# MomoinololuM3.net
KiCad netlist of a schematic drawn in EAGLE
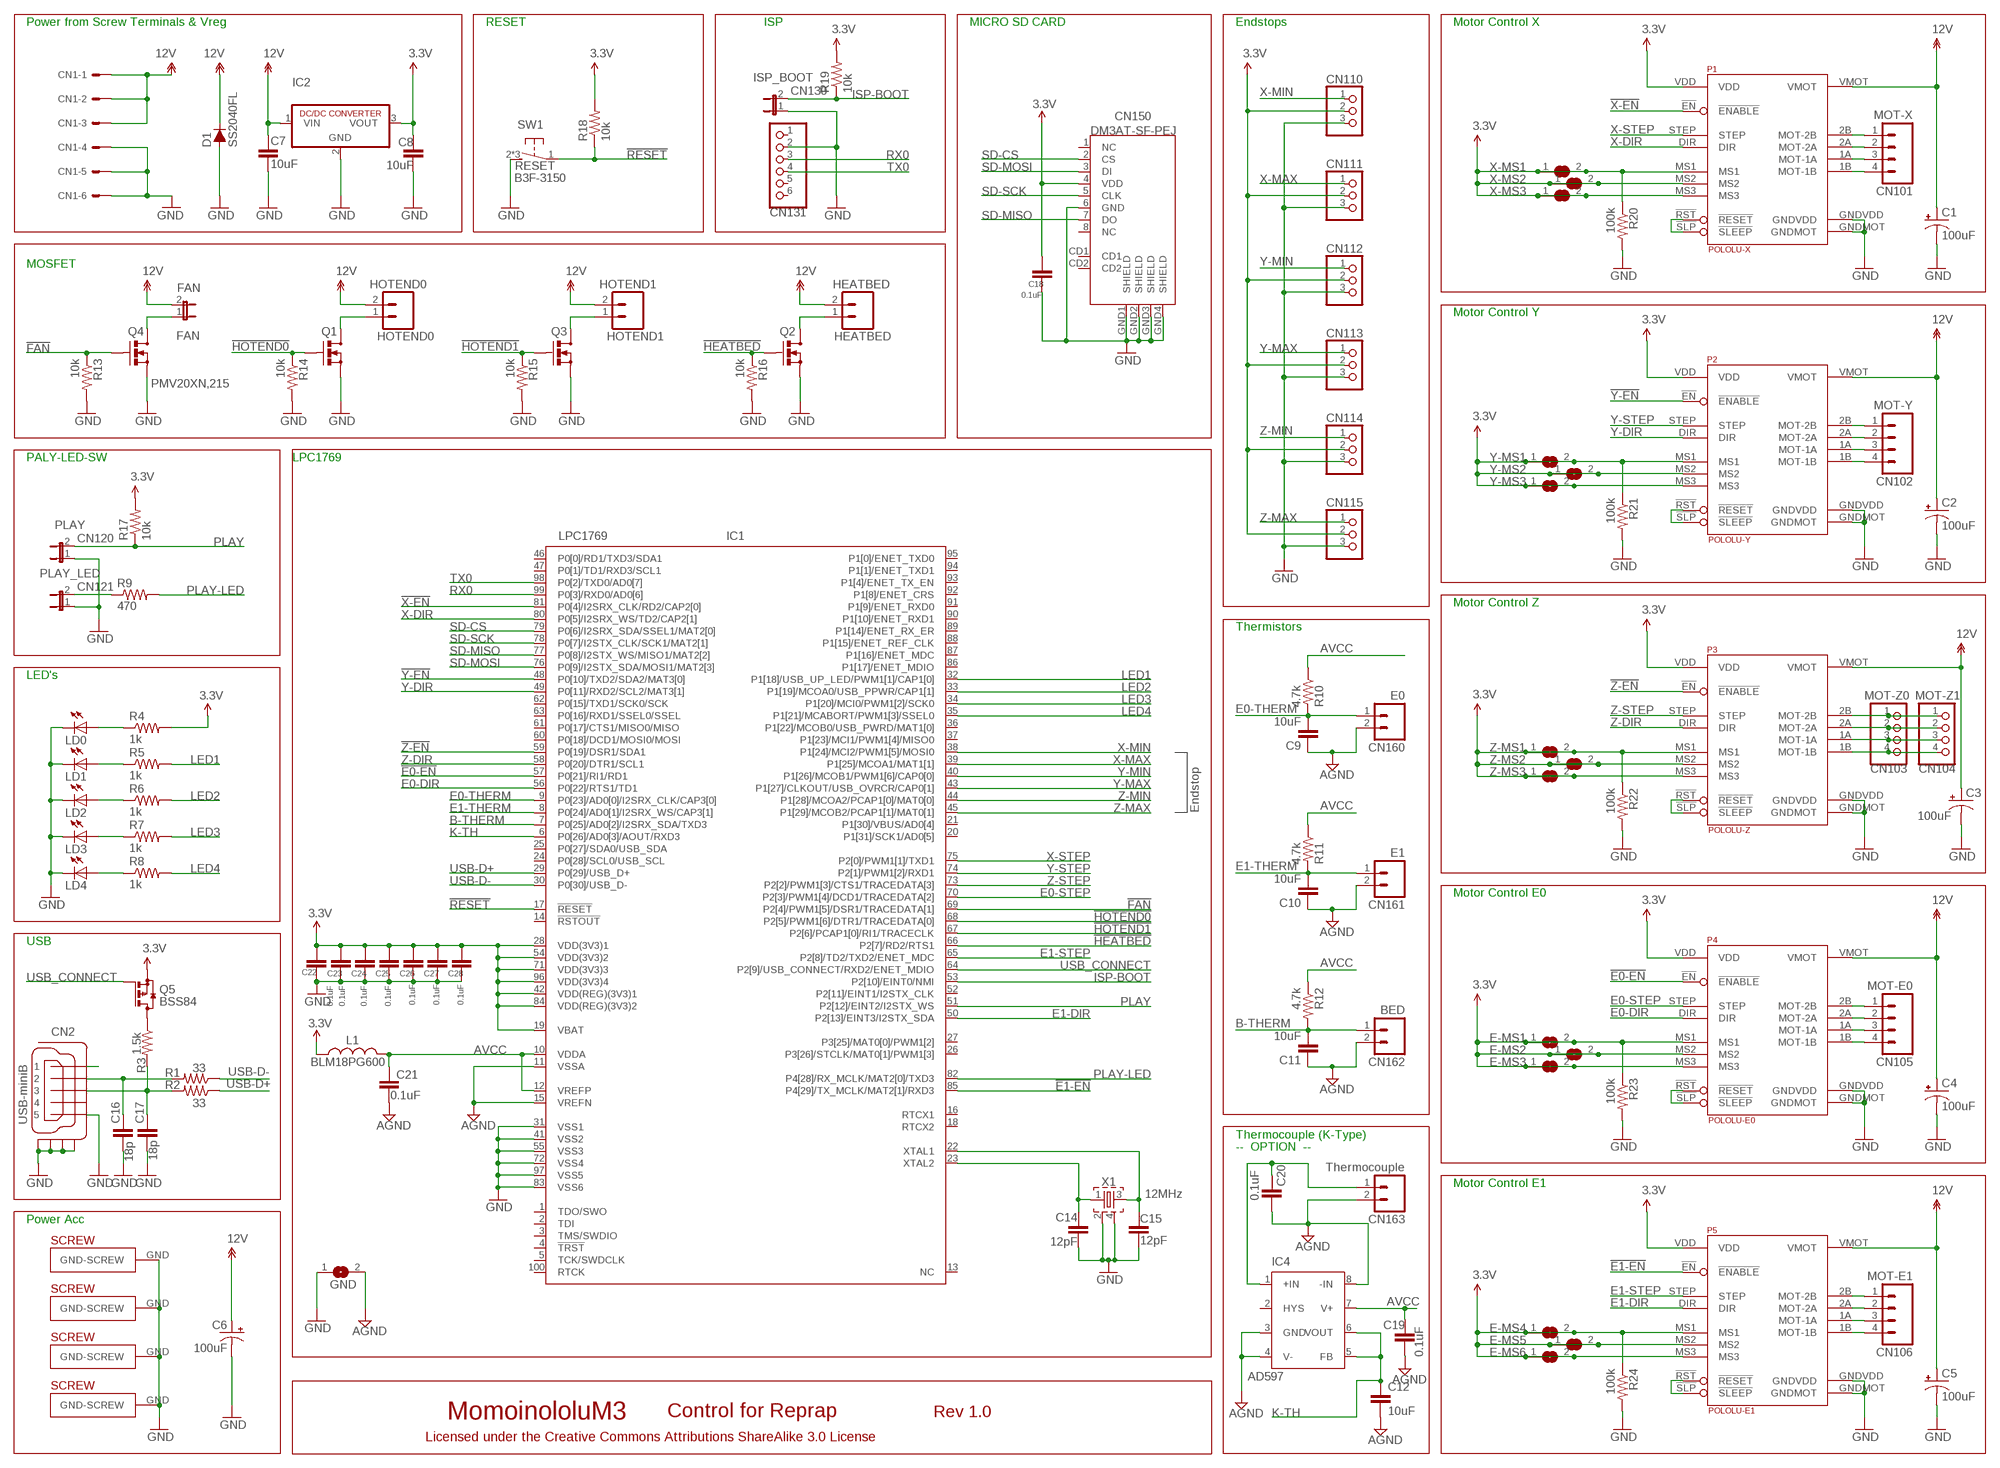
[diagram p0: schematic, sheet 1]

(export (version "E")
  (design (tool "Eeschema 10.0.6"))
  (components
    (comp (ref "C1")
      (value "100uF")
      (footprint "eagle-import:UD-6,3X7,7_NICHICON")
      (libsource (lib "eagle-import") (part "CPOL-USUD-6,3X7,7"))
    )
    (comp (ref "C2")
      (value "100uF")
      (footprint "eagle-import:UD-6,3X7,7_NICHICON")
      (libsource (lib "eagle-import") (part "CPOL-USUD-6,3X7,7"))
    )
    (comp (ref "C3")
      (value "100uF")
      (footprint "eagle-import:UD-6,3X7,7_NICHICON")
      (libsource (lib "eagle-import") (part "CPOL-USUD-6,3X7,7"))
    )
    (comp (ref "C4")
      (value "100uF")
      (footprint "eagle-import:UD-6,3X7,7_NICHICON")
      (libsource (lib "eagle-import") (part "CPOL-USUD-6,3X7,7"))
    )
    (comp (ref "C5")
      (value "100uF")
      (footprint "eagle-import:UD-6,3X7,7_NICHICON")
      (libsource (lib "eagle-import") (part "CPOL-USUD-6,3X7,7"))
    )
    (comp (ref "C6")
      (value "100uF")
      (footprint "eagle-import:UD-6,3X7,7_NICHICON")
      (libsource (lib "eagle-import") (part "CPOL-USUD-6,3X7,7"))
    )
    (comp (ref "C7")
      (value "10uF")
      (footprint "eagle-import:RCL_C1206K")
      (libsource (lib "eagle-import") (part "RCL_C-EUC1206K"))
    )
    (comp (ref "C8")
      (value "10uF")
      (footprint "eagle-import:RCL_C1206K")
      (libsource (lib "eagle-import") (part "RCL_C-EUC1206K"))
    )
    (comp (ref "C9")
      (value "10uF")
      (footprint "eagle-import:RCL_C1206K")
      (libsource (lib "eagle-import") (part "RCL_C-EUC1206K"))
    )
    (comp (ref "C10")
      (value "10uF")
      (footprint "eagle-import:RCL_C1206K")
      (libsource (lib "eagle-import") (part "RCL_C-EUC1206K"))
    )
    (comp (ref "C11")
      (value "10uF")
      (footprint "eagle-import:RCL_C1206K")
      (libsource (lib "eagle-import") (part "RCL_C-EUC1206K"))
    )
    (comp (ref "C12")
      (value "10uF")
      (footprint "eagle-import:RCL_C1206K")
      (libsource (lib "eagle-import") (part "RCL_C-EUC1206K"))
    )
    (comp (ref "C14")
      (value "12pF")
      (footprint "eagle-import:C0603")
      (libsource (lib "eagle-import") (part "C-EUC0603"))
    )
    (comp (ref "C15")
      (value "12pF")
      (footprint "eagle-import:C0603")
      (libsource (lib "eagle-import") (part "C-EUC0603"))
    )
    (comp (ref "C16")
      (value "18p")
      (footprint "eagle-import:C0603")
      (libsource (lib "eagle-import") (part "C-EUC0603"))
    )
    (comp (ref "C17")
      (value "18p")
      (footprint "eagle-import:C0603")
      (libsource (lib "eagle-import") (part "C-EUC0603"))
    )
    (comp (ref "C18")
      (value "0.1uF")
      (footprint "eagle-import:C0603")
      (libsource (lib "eagle-import") (part "C-EUC0603"))
    )
    (comp (ref "C19")
      (value "0.1uF")
      (footprint "eagle-import:C0603")
      (libsource (lib "eagle-import") (part "C-EUC0603"))
    )
    (comp (ref "C20")
      (value "0.1uF")
      (footprint "eagle-import:C0603")
      (libsource (lib "eagle-import") (part "C-EUC0603"))
    )
    (comp (ref "C21")
      (value "0.1uF")
      (footprint "eagle-import:C0603")
      (libsource (lib "eagle-import") (part "C-EUC0603"))
    )
    (comp (ref "C22")
      (value "0.1uF")
      (footprint "eagle-import:C0603")
      (libsource (lib "eagle-import") (part "C-EUC0603"))
    )
    (comp (ref "C23")
      (value "0.1uF")
      (footprint "eagle-import:C0603")
      (libsource (lib "eagle-import") (part "C-EUC0603"))
    )
    (comp (ref "C24")
      (value "0.1uF")
      (footprint "eagle-import:C0603")
      (libsource (lib "eagle-import") (part "C-EUC0603"))
    )
    (comp (ref "C25")
      (value "0.1uF")
      (footprint "eagle-import:C0603")
      (libsource (lib "eagle-import") (part "C-EUC0603"))
    )
    (comp (ref "C26")
      (value "0.1uF")
      (footprint "eagle-import:C0603")
      (libsource (lib "eagle-import") (part "C-EUC0603"))
    )
    (comp (ref "C27")
      (value "0.1uF")
      (footprint "eagle-import:C0603")
      (libsource (lib "eagle-import") (part "C-EUC0603"))
    )
    (comp (ref "C28")
      (value "0.1uF")
      (footprint "eagle-import:C0603")
      (libsource (lib "eagle-import") (part "C-EUC0603"))
    )
    (comp (ref "CN1")
      (value "556X-6H")
      (footprint "eagle-import:5569-6")
      (libsource (lib "eagle-import") (part "556X-6H"))
    )
    (comp (ref "CN2")
      (value "USB-miniB")
      (footprint "eagle-import:CON-HIROSE_UX60A-MB-5ST")
      (libsource (lib "eagle-import") (part "CON-HIROSE_MINI-USB-SHIELD-UX60A-MB-5ST"))
    )
    (comp (ref "CN101")
      (value "MOT-X")
      (footprint "eagle-import:SPARKFUN_MOLEX-1X4")
      (libsource (lib "eagle-import") (part "SPARKFUN_M04POLAR"))
    )
    (comp (ref "CN102")
      (value "MOT-Y")
      (footprint "eagle-import:SPARKFUN_MOLEX-1X4")
      (libsource (lib "eagle-import") (part "SPARKFUN_M04POLAR"))
    )
    (comp (ref "CN103")
      (value "MOT-Z0")
      (footprint "eagle-import:1X04")
      (libsource (lib "eagle-import") (part "PINHD-1X4"))
    )
    (comp (ref "CN104")
      (value "MOT-Z1")
      (footprint "eagle-import:1X04")
      (libsource (lib "eagle-import") (part "PINHD-1X4"))
    )
    (comp (ref "CN105")
      (value "MOT-E0")
      (footprint "eagle-import:SPARKFUN_MOLEX-1X4")
      (libsource (lib "eagle-import") (part "SPARKFUN_M04POLAR"))
    )
    (comp (ref "CN106")
      (value "MOT-E1")
      (footprint "eagle-import:SPARKFUN_MOLEX-1X4")
      (libsource (lib "eagle-import") (part "SPARKFUN_M04POLAR"))
    )
    (comp (ref "CN110")
      (value "PINHD-1X3")
      (footprint "eagle-import:1X03")
      (libsource (lib "eagle-import") (part "PINHD-1X3"))
    )
    (comp (ref "CN111")
      (value "PINHD-1X3")
      (footprint "eagle-import:1X03")
      (libsource (lib "eagle-import") (part "PINHD-1X3"))
    )
    (comp (ref "CN112")
      (value "PINHD-1X3")
      (footprint "eagle-import:1X03")
      (libsource (lib "eagle-import") (part "PINHD-1X3"))
    )
    (comp (ref "CN113")
      (value "PINHD-1X3")
      (footprint "eagle-import:1X03")
      (libsource (lib "eagle-import") (part "PINHD-1X3"))
    )
    (comp (ref "CN114")
      (value "PINHD-1X3")
      (footprint "eagle-import:1X03")
      (libsource (lib "eagle-import") (part "PINHD-1X3"))
    )
    (comp (ref "CN115")
      (value "PINHD-1X3")
      (footprint "eagle-import:1X03")
      (libsource (lib "eagle-import") (part "PINHD-1X3"))
    )
    (comp (ref "CN120")
      (value "PLAY")
      (footprint "eagle-import:SPARKFUN_1X02")
      (libsource (lib "eagle-import") (part "SPARKFUN_JUMPER-2PTH"))
    )
    (comp (ref "CN121")
      (value "PLAY_LED")
      (footprint "eagle-import:SPARKFUN_1X02")
      (libsource (lib "eagle-import") (part "SPARKFUN_JUMPER-2PTH"))
    )
    (comp (ref "CN130")
      (value "ISP_BOOT")
      (footprint "eagle-import:SPARKFUN_1X02")
      (libsource (lib "eagle-import") (part "SPARKFUN_JUMPER-2PTH"))
    )
    (comp (ref "CN131")
      (value "PINHD-1X6")
      (footprint "eagle-import:1X06")
      (libsource (lib "eagle-import") (part "PINHD-1X6"))
    )
    (comp (ref "CN150")
      (value "DM3AT-SF-PEJ")
      (footprint "eagle-import:DM3AT-SF-PEJ")
      (libsource (lib "eagle-import") (part "DM3AT-SF-PEJ"))
    )
    (comp (ref "CN160")
      (value "E0")
      (footprint "eagle-import:SPARKFUN_1X02")
      (libsource (lib "eagle-import") (part "momoinololuM3_SPARKFUN_M02PTH"))
    )
    (comp (ref "CN161")
      (value "E1")
      (footprint "eagle-import:SPARKFUN_1X02")
      (libsource (lib "eagle-import") (part "momoinololuM3_SPARKFUN_M02PTH"))
    )
    (comp (ref "CN162")
      (value "BED")
      (footprint "eagle-import:SPARKFUN_1X02")
      (libsource (lib "eagle-import") (part "momoinololuM3_SPARKFUN_M02PTH"))
    )
    (comp (ref "CN163")
      (value "Thermocouple")
      (footprint "eagle-import:SPARKFUN_1X02")
      (libsource (lib "eagle-import") (part "momoinololuM3_SPARKFUN_M02PTH"))
    )
    (comp (ref "D1")
      (value "SS2040FL")
      (footprint "eagle-import:SEMICON-SMD-IPC_SOD123")
      (libsource (lib "eagle-import") (part "SEMICON-SMD-IPC_D-FILL-SOD123"))
    )
    (comp (ref "E-MS1")
      (value "SJ")
      (footprint "eagle-import:SJ")
      (libsource (lib "eagle-import") (part "SJ"))
    )
    (comp (ref "E-MS2")
      (value "SJ")
      (footprint "eagle-import:SJ")
      (libsource (lib "eagle-import") (part "SJ"))
    )
    (comp (ref "E-MS3")
      (value "SJ")
      (footprint "eagle-import:SJ")
      (libsource (lib "eagle-import") (part "SJ"))
    )
    (comp (ref "E-MS4")
      (value "SJ")
      (footprint "eagle-import:SJ")
      (libsource (lib "eagle-import") (part "SJ"))
    )
    (comp (ref "E-MS5")
      (value "SJ")
      (footprint "eagle-import:SJ")
      (libsource (lib "eagle-import") (part "SJ"))
    )
    (comp (ref "E-MS6")
      (value "SJ")
      (footprint "eagle-import:SJ")
      (libsource (lib "eagle-import") (part "SJ"))
    )
    (comp (ref "FAN")
      (value "FAN")
      (footprint "eagle-import:SPARKFUN_1X02")
      (libsource (lib "eagle-import") (part "SPARKFUN_JUMPER-2PTH"))
    )
    (comp (ref "GND") (value "SJ") (footprint "eagle-import:SJ") (libsource (lib "eagle-import") (part "SJ")))
    (comp (ref "HEATBED")
      (value "HEATBED")
      (footprint "eagle-import:SCREWTERMINAL-5.08MM-2")
      (libsource (lib "eagle-import") (part "SPARKFUN_M025.08MM"))
    )
    (comp (ref "HOLE1")
      (value "PLATED-SCREW")
      (footprint "eagle-import:PLATEDSCREW")
      (libsource (lib "eagle-import") (part "PLATED-SCREW"))
    )
    (comp (ref "HOLE2")
      (value "PLATED-SCREW")
      (footprint "eagle-import:PLATEDSCREW")
      (libsource (lib "eagle-import") (part "PLATED-SCREW"))
    )
    (comp (ref "HOLE3")
      (value "PLATED-SCREW")
      (footprint "eagle-import:PLATEDSCREW")
      (libsource (lib "eagle-import") (part "PLATED-SCREW"))
    )
    (comp (ref "HOLE4")
      (value "PLATED-SCREW")
      (footprint "eagle-import:PLATEDSCREW")
      (libsource (lib "eagle-import") (part "PLATED-SCREW"))
    )
    (comp (ref "HOTEND0")
      (value "HOTEND0")
      (footprint "eagle-import:SCREWTERMINAL-5.08MM-2")
      (libsource (lib "eagle-import") (part "SPARKFUN_M025.08MM"))
    )
    (comp (ref "HOTEND1")
      (value "HOTEND1")
      (footprint "eagle-import:SCREWTERMINAL-5.08MM-2")
      (libsource (lib "eagle-import") (part "SPARKFUN_M025.08MM"))
    )
    (comp (ref "IC1")
      (value "LPC1769")
      (footprint "eagle-import:LQFP100-14X14")
      (libsource (lib "eagle-import") (part "LPC1768"))
    )
    (comp (ref "IC2")
      (value "R-78E3.3-0.5")
      (footprint "eagle-import:SIP3")
      (libsource (lib "eagle-import") (part "R-78C-1.03.3"))
    )
    (comp (ref "IC4")
      (value "AD597")
      (footprint "eagle-import:SO8")
      (libsource (lib "eagle-import") (part "AD597"))
    )
    (comp (ref "L1")
      (value "BLM18PG600")
      (footprint "eagle-import:L2012C")
      (libsource (lib "eagle-import") (part "L-USL2012C"))
    )
    (comp (ref "LD0")
      (value "LEDSML0805")
      (footprint "eagle-import:SML0805")
      (libsource (lib "eagle-import") (part "LEDSML0805"))
    )
    (comp (ref "LD1")
      (value "LEDSML0805")
      (footprint "eagle-import:SML0805")
      (libsource (lib "eagle-import") (part "LEDSML0805"))
    )
    (comp (ref "LD2")
      (value "LEDSML0805")
      (footprint "eagle-import:SML0805")
      (libsource (lib "eagle-import") (part "LEDSML0805"))
    )
    (comp (ref "LD3")
      (value "LEDSML0805")
      (footprint "eagle-import:SML0805")
      (libsource (lib "eagle-import") (part "LEDSML0805"))
    )
    (comp (ref "LD4")
      (value "LEDSML0805")
      (footprint "eagle-import:SML0805")
      (libsource (lib "eagle-import") (part "LEDSML0805"))
    )
    (comp (ref "P1")
      (value "POLOLU-X")
      (footprint "eagle-import:POLOLU-ALLEGRO_POLOLU-ALLEGRO-PTH")
      (libsource (lib "eagle-import") (part "POLOLU-ALLEGRO_POLOLU-ALLEGRO"))
    )
    (comp (ref "P2")
      (value "POLOLU-Y")
      (footprint "eagle-import:POLOLU-ALLEGRO_POLOLU-ALLEGRO-PTH")
      (libsource (lib "eagle-import") (part "POLOLU-ALLEGRO_POLOLU-ALLEGRO"))
    )
    (comp (ref "P3")
      (value "POLOLU-Z")
      (footprint "eagle-import:POLOLU-ALLEGRO_POLOLU-ALLEGRO-PTH")
      (libsource (lib "eagle-import") (part "POLOLU-ALLEGRO_POLOLU-ALLEGRO"))
    )
    (comp (ref "P4")
      (value "POLOLU-E0")
      (footprint "eagle-import:POLOLU-ALLEGRO_POLOLU-ALLEGRO-PTH")
      (libsource (lib "eagle-import") (part "POLOLU-ALLEGRO_POLOLU-ALLEGRO"))
    )
    (comp (ref "P5")
      (value "POLOLU-E1")
      (footprint "eagle-import:POLOLU-ALLEGRO_POLOLU-ALLEGRO-PTH")
      (libsource (lib "eagle-import") (part "POLOLU-ALLEGRO_POLOLU-ALLEGRO"))
    )
    (comp (ref "Q1")
      (value "PSMN038-100YLX")
      (footprint "eagle-import:SOT669")
      (libsource (lib "eagle-import") (part "SPARKFUN_MOSFET-NCHANNELSOT669"))
    )
    (comp (ref "Q2")
      (value "PSMN038-100YLX")
      (footprint "eagle-import:SOT669")
      (libsource (lib "eagle-import") (part "SPARKFUN_MOSFET-NCHANNELSOT669"))
    )
    (comp (ref "Q3")
      (value "PSMN038-100YLX")
      (footprint "eagle-import:SOT669")
      (libsource (lib "eagle-import") (part "SPARKFUN_MOSFET-NCHANNELSOT669"))
    )
    (comp (ref "Q4")
      (value "PMV20XN,215")
      (footprint "eagle-import:SPARKFUN_SOT23-3")
      (libsource (lib "eagle-import") (part "momoinololuM3_SPARKFUN_MOSFET-NCHANNELSMD"))
    )
    (comp (ref "Q5")
      (value "BSS84")
      (footprint "eagle-import:SOT23")
      (libsource (lib "eagle-import") (part "BSS84"))
    )
    (comp (ref "R1")
      (value "33")
      (footprint "eagle-import:R0603")
      (libsource (lib "eagle-import") (part "R-US_R0603"))
    )
    (comp (ref "R2")
      (value "33")
      (footprint "eagle-import:R0603")
      (libsource (lib "eagle-import") (part "R-US_R0603"))
    )
    (comp (ref "R3")
      (value "1.5k")
      (footprint "eagle-import:R0603")
      (libsource (lib "eagle-import") (part "R-US_R0603"))
    )
    (comp (ref "R4")
      (value "1k")
      (footprint "eagle-import:R0603")
      (libsource (lib "eagle-import") (part "R-US_R0603"))
    )
    (comp (ref "R5")
      (value "1k")
      (footprint "eagle-import:R0603")
      (libsource (lib "eagle-import") (part "R-US_R0603"))
    )
    (comp (ref "R6")
      (value "1k")
      (footprint "eagle-import:R0603")
      (libsource (lib "eagle-import") (part "R-US_R0603"))
    )
    (comp (ref "R7")
      (value "1k")
      (footprint "eagle-import:R0603")
      (libsource (lib "eagle-import") (part "R-US_R0603"))
    )
    (comp (ref "R8")
      (value "1k")
      (footprint "eagle-import:R0603")
      (libsource (lib "eagle-import") (part "R-US_R0603"))
    )
    (comp (ref "R9")
      (value "470")
      (footprint "eagle-import:R0603")
      (libsource (lib "eagle-import") (part "R-US_R0603"))
    )
    (comp (ref "R10")
      (value "4.7k")
      (footprint "eagle-import:R0603")
      (libsource (lib "eagle-import") (part "R-US_R0603"))
    )
    (comp (ref "R11")
      (value "4.7k")
      (footprint "eagle-import:R0603")
      (libsource (lib "eagle-import") (part "R-US_R0603"))
    )
    (comp (ref "R12")
      (value "4.7k")
      (footprint "eagle-import:R0603")
      (libsource (lib "eagle-import") (part "R-US_R0603"))
    )
    (comp (ref "R13")
      (value "10k")
      (footprint "eagle-import:R0603")
      (libsource (lib "eagle-import") (part "R-US_R0603"))
    )
    (comp (ref "R14")
      (value "10k")
      (footprint "eagle-import:R0603")
      (libsource (lib "eagle-import") (part "R-US_R0603"))
    )
    (comp (ref "R15")
      (value "10k")
      (footprint "eagle-import:R0603")
      (libsource (lib "eagle-import") (part "R-US_R0603"))
    )
    (comp (ref "R16")
      (value "10k")
      (footprint "eagle-import:R0603")
      (libsource (lib "eagle-import") (part "R-US_R0603"))
    )
    (comp (ref "R17")
      (value "10k")
      (footprint "eagle-import:R0603")
      (libsource (lib "eagle-import") (part "R-US_R0603"))
    )
    (comp (ref "R18")
      (value "10k")
      (footprint "eagle-import:R0603")
      (libsource (lib "eagle-import") (part "R-US_R0603"))
    )
    (comp (ref "R19")
      (value "10k")
      (footprint "eagle-import:R0603")
      (libsource (lib "eagle-import") (part "R-US_R0603"))
    )
    (comp (ref "R20")
      (value "100k")
      (footprint "eagle-import:R0603")
      (libsource (lib "eagle-import") (part "R-US_R0603"))
    )
    (comp (ref "R21")
      (value "100k")
      (footprint "eagle-import:R0603")
      (libsource (lib "eagle-import") (part "R-US_R0603"))
    )
    (comp (ref "R22")
      (value "100k")
      (footprint "eagle-import:R0603")
      (libsource (lib "eagle-import") (part "R-US_R0603"))
    )
    (comp (ref "R23")
      (value "100k")
      (footprint "eagle-import:R0603")
      (libsource (lib "eagle-import") (part "R-US_R0603"))
    )
    (comp (ref "R24")
      (value "100k")
      (footprint "eagle-import:R0603")
      (libsource (lib "eagle-import") (part "R-US_R0603"))
    )
    (comp (ref "SW1")
      (value "B3F-3150")
      (footprint "eagle-import:B3F-31XX")
      (fields (field (name "MPN") "B3F-3100"))
      (libsource (lib "eagle-import") (part "31-XX"))
    )
    (comp (ref "X-MS1")
      (value "SJ")
      (footprint "eagle-import:SJ")
      (libsource (lib "eagle-import") (part "SJ"))
    )
    (comp (ref "X-MS2")
      (value "SJ")
      (footprint "eagle-import:SJ")
      (libsource (lib "eagle-import") (part "SJ"))
    )
    (comp (ref "X-MS3")
      (value "SJ")
      (footprint "eagle-import:SJ")
      (libsource (lib "eagle-import") (part "SJ"))
    )
    (comp (ref "X1")
      (value "12MHz")
      (footprint "eagle-import:FA-238")
      (libsource (lib "eagle-import") (part "FA-238"))
    )
    (comp (ref "Y-MS1")
      (value "SJ")
      (footprint "eagle-import:SJ")
      (libsource (lib "eagle-import") (part "SJ"))
    )
    (comp (ref "Y-MS2")
      (value "SJ")
      (footprint "eagle-import:SJ")
      (libsource (lib "eagle-import") (part "SJ"))
    )
    (comp (ref "Y-MS3")
      (value "SJ")
      (footprint "eagle-import:SJ")
      (libsource (lib "eagle-import") (part "SJ"))
    )
    (comp (ref "Z-MS1")
      (value "SJ")
      (footprint "eagle-import:SJ")
      (libsource (lib "eagle-import") (part "SJ"))
    )
    (comp (ref "Z-MS2")
      (value "SJ")
      (footprint "eagle-import:SJ")
      (libsource (lib "eagle-import") (part "SJ"))
    )
    (comp (ref "Z-MS3")
      (value "SJ")
      (footprint "eagle-import:SJ")
      (libsource (lib "eagle-import") (part "SJ"))
    )
  )
  (nets
    (net (code "1") (name "/AVCC") (class "Default")
      (node (ref "C19") (pin "1") (pinfunction "1_1") (pintype "passive"))
      (node (ref "C21") (pin "1") (pinfunction "1_1") (pintype "passive"))
      (node (ref "IC1") (pin "10") (pinfunction "VDDA_10") (pintype "bidirectional"))
      (node (ref "IC1") (pin "12") (pinfunction "VREFP_12") (pintype "bidirectional"))
      (node (ref "IC4") (pin "7") (pinfunction "V+_7") (pintype "power_in"))
      (node (ref "L1") (pin "2") (pinfunction "2_2") (pintype "passive"))
      (node (ref "R10") (pin "1") (pinfunction "1_1") (pintype "passive"))
      (node (ref "R11") (pin "1") (pinfunction "1_1") (pintype "passive"))
      (node (ref "R12") (pin "1") (pinfunction "1_1") (pintype "passive"))
    )
    (net (code "2") (name "/B-THERM") (class "Default")
      (node (ref "C11") (pin "2") (pinfunction "2_2") (pintype "passive"))
      (node (ref "CN162") (pin "1") (pinfunction "1_1") (pintype "passive"))
      (node (ref "IC1") (pin "7") (pinfunction "P0[25]/AD0[2]/I2SRX_SDA/TXD3_7") (pintype "bidirectional"))
      (node (ref "R12") (pin "2") (pinfunction "2_2") (pintype "passive"))
    )
    (net (code "3") (name "/E0-DIR") (class "Default")
      (node (ref "IC1") (pin "56") (pinfunction "P0[22]/RTS1/TD1_56") (pintype "bidirectional"))
      (node (ref "P4") (pin "DIR") (pinfunction "DIR_DIR") (pintype "bidirectional"))
    )
    (net (code "4") (name "/E0-STEP") (class "Default")
      (node (ref "IC1") (pin "70") (pinfunction "P2[3]/PWM1[4]/DCD1/TRACEDATA[2]_70") (pintype "bidirectional"))
      (node (ref "P4") (pin "STEP") (pinfunction "STEP_STEP") (pintype "bidirectional"))
    )
    (net (code "5") (name "/E0-THERM") (class "Default")
      (node (ref "C9") (pin "2") (pinfunction "2_2") (pintype "passive"))
      (node (ref "CN160") (pin "1") (pinfunction "1_1") (pintype "passive"))
      (node (ref "IC1") (pin "9") (pinfunction "P0[23]/AD0[0]/I2SRX_CLK/CAP3[0]_9") (pintype "bidirectional"))
      (node (ref "R10") (pin "2") (pinfunction "2_2") (pintype "passive"))
    )
    (net (code "6") (name "/E1-DIR") (class "Default")
      (node (ref "IC1") (pin "50") (pinfunction "P2[13]/EINT3/I2STX_SDA_50") (pintype "bidirectional"))
      (node (ref "P5") (pin "DIR") (pinfunction "DIR_DIR") (pintype "bidirectional"))
    )
    (net (code "7") (name "/E1-STEP") (class "Default")
      (node (ref "IC1") (pin "65") (pinfunction "P2[8]/TD2/TXD2/ENET_MDC_65") (pintype "bidirectional"))
      (node (ref "P5") (pin "STEP") (pinfunction "STEP_STEP") (pintype "bidirectional"))
    )
    (net (code "8") (name "/E1-THERM") (class "Default")
      (node (ref "C10") (pin "2") (pinfunction "2_2") (pintype "passive"))
      (node (ref "CN161") (pin "1") (pinfunction "1_1") (pintype "passive"))
      (node (ref "IC1") (pin "8") (pinfunction "P0[24]/AD0[1]/I2SRX_WS/CAP3[1]_8") (pintype "bidirectional"))
      (node (ref "R11") (pin "2") (pinfunction "2_2") (pintype "passive"))
    )
    (net (code "9") (name "/ISP-BOOT") (class "Default")
      (node (ref "CN130") (pin "2") (pinfunction "2_2") (pintype "passive"))
      (node (ref "IC1") (pin "53") (pinfunction "P2[10]/EINT0/NMI_53") (pintype "bidirectional"))
      (node (ref "R19") (pin "1") (pinfunction "1_1") (pintype "passive"))
    )
    (net (code "10") (name "/K-TH") (class "Default")
      (node (ref "C12") (pin "1") (pinfunction "1_1") (pintype "passive"))
      (node (ref "IC1") (pin "6") (pinfunction "P0[26]/AD0[3]/AOUT/RXD3_6") (pintype "bidirectional"))
      (node (ref "IC4") (pin "5") (pinfunction "FB_5") (pintype "bidirectional"))
      (node (ref "IC4") (pin "6") (pinfunction "VOUT_6") (pintype "bidirectional"))
    )
    (net (code "11") (name "/LED1") (class "Default")
      (node (ref "IC1") (pin "32") (pinfunction "P1[18]/USB_UP_LED/PWM1[1]/CAP1[0]_32") (pintype "bidirectional"))
      (node (ref "R5") (pin "2") (pinfunction "2_2") (pintype "passive"))
    )
    (net (code "12") (name "/LED2") (class "Default")
      (node (ref "IC1") (pin "33") (pinfunction "P1[19]/MCOA0/USB_PPWR/CAP1[1]_33") (pintype "bidirectional"))
      (node (ref "R6") (pin "2") (pinfunction "2_2") (pintype "passive"))
    )
    (net (code "13") (name "/LED3") (class "Default")
      (node (ref "IC1") (pin "34") (pinfunction "P1[20]/MCI0/PWM1[2]/SCK0_34") (pintype "bidirectional"))
      (node (ref "R7") (pin "2") (pinfunction "2_2") (pintype "passive"))
    )
    (net (code "14") (name "/LED4") (class "Default")
      (node (ref "IC1") (pin "35") (pinfunction "P1[21]/MCABORT/PWM1[3]/SSEL0_35") (pintype "bidirectional"))
      (node (ref "R8") (pin "2") (pinfunction "2_2") (pintype "passive"))
    )
    (net (code "15") (name "/PLAY") (class "Default")
      (node (ref "CN120") (pin "2") (pinfunction "2_2") (pintype "passive"))
      (node (ref "IC1") (pin "51") (pinfunction "P2[12]/EINT2/I2STX_WS_51") (pintype "bidirectional"))
      (node (ref "R17") (pin "1") (pinfunction "1_1") (pintype "passive"))
    )
    (net (code "16") (name "/PLAY-LED") (class "Default")
      (node (ref "IC1") (pin "82") (pinfunction "P4[28]/RX_MCLK/MAT2[0]/TXD3_82") (pintype "bidirectional"))
      (node (ref "R9") (pin "2") (pinfunction "2_2") (pintype "passive"))
    )
    (net (code "17") (name "/RX0") (class "Default")
      (node (ref "CN131") (pin "3") (pinfunction "3_3") (pintype "passive"))
      (node (ref "IC1") (pin "99") (pinfunction "P0[3]/RXD0/AD0[6]_99") (pintype "bidirectional"))
    )
    (net (code "18") (name "/SD-CS") (class "Default")
      (node (ref "CN150") (pin "2") (pinfunction "CS_2") (pintype "bidirectional"))
      (node (ref "IC1") (pin "79") (pinfunction "P0[6]/I2SRX_SDA/SSEL1/MAT2[0]_79") (pintype "bidirectional"))
    )
    (net (code "19") (name "/SD-MISO") (class "Default")
      (node (ref "CN150") (pin "7") (pinfunction "DO_7") (pintype "bidirectional"))
      (node (ref "IC1") (pin "77") (pinfunction "P0[8]/I2STX_WS/MISO1/MAT2[2]_77") (pintype "bidirectional"))
    )
    (net (code "20") (name "/SD-MOSI") (class "Default")
      (node (ref "CN150") (pin "3") (pinfunction "DI_3") (pintype "bidirectional"))
      (node (ref "IC1") (pin "76") (pinfunction "P0[9]/I2STX_SDA/MOSI1/MAT2[3]_76") (pintype "bidirectional"))
    )
    (net (code "21") (name "/SD-SCK") (class "Default")
      (node (ref "CN150") (pin "5") (pinfunction "CLK_5") (pintype "bidirectional"))
      (node (ref "IC1") (pin "78") (pinfunction "P0[7]/I2STX_CLK/SCK1/MAT2[1]_78") (pintype "bidirectional"))
    )
    (net (code "22") (name "/TX0") (class "Default")
      (node (ref "CN131") (pin "4") (pinfunction "4_4") (pintype "passive"))
      (node (ref "IC1") (pin "98") (pinfunction "P0[2]/TXD0/AD0[7]_98") (pintype "bidirectional"))
    )
    (net (code "23") (name "/USB-D+") (class "Default")
      (node (ref "IC1") (pin "29") (pinfunction "P0[29]/USB_D+_29") (pintype "bidirectional"))
      (node (ref "R2") (pin "1") (pinfunction "1_1") (pintype "passive"))
    )
    (net (code "24") (name "/USB-D-") (class "Default")
      (node (ref "IC1") (pin "30") (pinfunction "P0[30]/USB_D-_30") (pintype "bidirectional"))
      (node (ref "R1") (pin "1") (pinfunction "1_1") (pintype "passive"))
    )
    (net (code "25") (name "/USB_CONNECT") (class "Default")
      (node (ref "IC1") (pin "64") (pinfunction "P2[9]/USB_CONNECT/RXD2/ENET_MDIO_64") (pintype "bidirectional"))
      (node (ref "Q5") (pin "1") (pinfunction "G_1") (pintype "passive"))
    )
    (net (code "26") (name "/X-DIR") (class "Default")
      (node (ref "IC1") (pin "80") (pinfunction "P0[5]/I2SRX_WS/TD2/CAP2[1]_80") (pintype "bidirectional"))
      (node (ref "P1") (pin "DIR") (pinfunction "DIR_DIR") (pintype "bidirectional"))
    )
    (net (code "27") (name "/X-MAX") (class "Default")
      (node (ref "CN111") (pin "1") (pinfunction "1_1") (pintype "passive"))
      (node (ref "IC1") (pin "39") (pinfunction "P1[25]/MCOA1/MAT1[1]_39") (pintype "bidirectional"))
    )
    (net (code "28") (name "/X-MIN") (class "Default")
      (node (ref "CN110") (pin "1") (pinfunction "1_1") (pintype "passive"))
      (node (ref "IC1") (pin "38") (pinfunction "P1[24]/MCI2/PWM1[5]/MOSI0_38") (pintype "bidirectional"))
    )
    (net (code "29") (name "/X-STEP") (class "Default")
      (node (ref "IC1") (pin "75") (pinfunction "P2[0]/PWM1[1]/TXD1_75") (pintype "bidirectional"))
      (node (ref "P1") (pin "STEP") (pinfunction "STEP_STEP") (pintype "bidirectional"))
    )
    (net (code "30") (name "/Y-DIR") (class "Default")
      (node (ref "IC1") (pin "49") (pinfunction "P0[11]/RXD2/SCL2/MAT3[1]_49") (pintype "bidirectional"))
      (node (ref "P2") (pin "DIR") (pinfunction "DIR_DIR") (pintype "bidirectional"))
    )
    (net (code "31") (name "/Y-MAX") (class "Default")
      (node (ref "CN113") (pin "1") (pinfunction "1_1") (pintype "passive"))
      (node (ref "IC1") (pin "43") (pinfunction "P1[27]/CLKOUT/USB_OVRCR/CAP0[1]_43") (pintype "bidirectional"))
    )
    (net (code "32") (name "/Y-MIN") (class "Default")
      (node (ref "CN112") (pin "1") (pinfunction "1_1") (pintype "passive"))
      (node (ref "IC1") (pin "40") (pinfunction "P1[26]/MCOB1/PWM1[6]/CAP0[0]_40") (pintype "bidirectional"))
    )
    (net (code "33") (name "/Y-STEP") (class "Default")
      (node (ref "IC1") (pin "74") (pinfunction "P2[1]/PWM1[2]/RXD1_74") (pintype "bidirectional"))
      (node (ref "P2") (pin "STEP") (pinfunction "STEP_STEP") (pintype "bidirectional"))
    )
    (net (code "34") (name "/Z-DIR") (class "Default")
      (node (ref "IC1") (pin "58") (pinfunction "P0[20]/DTR1/SCL1_58") (pintype "bidirectional"))
      (node (ref "P3") (pin "DIR") (pinfunction "DIR_DIR") (pintype "bidirectional"))
    )
    (net (code "35") (name "/Z-MAX") (class "Default")
      (node (ref "CN115") (pin "1") (pinfunction "1_1") (pintype "passive"))
      (node (ref "IC1") (pin "45") (pinfunction "P1[29]/MCOB2/PCAP1[1]/MAT0[1]_45") (pintype "bidirectional"))
    )
    (net (code "36") (name "/Z-MIN") (class "Default")
      (node (ref "CN114") (pin "1") (pinfunction "1_1") (pintype "passive"))
      (node (ref "IC1") (pin "44") (pinfunction "P1[28]/MCOA2/PCAP1[0]/MAT0[0]_44") (pintype "bidirectional"))
    )
    (net (code "37") (name "/Z-STEP") (class "Default")
      (node (ref "IC1") (pin "73") (pinfunction "P2[2]/PWM1[3]/CTS1/TRACEDATA[3]_73") (pintype "bidirectional"))
      (node (ref "P3") (pin "STEP") (pinfunction "STEP_STEP") (pintype "bidirectional"))
    )
    (net (code "38") (name "/~{E0-EN}") (class "Default")
      (node (ref "IC1") (pin "57") (pinfunction "P0[21]/RI1/RD1_57") (pintype "bidirectional"))
      (node (ref "P4") (pin "!EN") (pinfunction "~{ENABLE}_!EN") (pintype "input"))
    )
    (net (code "39") (name "/~{E1-EN}") (class "Default")
      (node (ref "IC1") (pin "85") (pinfunction "P4[29]/TX_MCLK/MAT2[1]/RXD3_85") (pintype "bidirectional"))
      (node (ref "P5") (pin "!EN") (pinfunction "~{ENABLE}_!EN") (pintype "input"))
    )
    (net (code "40") (name "/~{FAN}") (class "Default")
      (node (ref "IC1") (pin "69") (pinfunction "P2[4]/PWM1[5]/DSR1/TRACEDATA[1]_69") (pintype "bidirectional"))
      (node (ref "Q4") (pin "1") (pinfunction "G_1") (pintype "passive"))
      (node (ref "R13") (pin "1") (pinfunction "1_1") (pintype "passive"))
    )
    (net (code "41") (name "/~{HEATBED}") (class "Default")
      (node (ref "IC1") (pin "66") (pinfunction "P2[7]/RD2/RTS1_66") (pintype "bidirectional"))
      (node (ref "Q2") (pin "4") (pinfunction "G_4") (pintype "passive"))
      (node (ref "R16") (pin "1") (pinfunction "1_1") (pintype "passive"))
    )
    (net (code "42") (name "/~{HOTEND0}") (class "Default")
      (node (ref "IC1") (pin "68") (pinfunction "P2[5]/PWM1[6]/DTR1/TRACEDATA[0]_68") (pintype "bidirectional"))
      (node (ref "Q1") (pin "4") (pinfunction "G_4") (pintype "passive"))
      (node (ref "R14") (pin "1") (pinfunction "1_1") (pintype "passive"))
    )
    (net (code "43") (name "/~{HOTEND1}") (class "Default")
      (node (ref "IC1") (pin "67") (pinfunction "P2[6]/PCAP1[0]/RI1/TRACECLK_67") (pintype "bidirectional"))
      (node (ref "Q3") (pin "4") (pinfunction "G_4") (pintype "passive"))
      (node (ref "R15") (pin "1") (pinfunction "1_1") (pintype "passive"))
    )
    (net (code "44") (name "/~{RESET}") (class "Default")
      (node (ref "IC1") (pin "17") (pinfunction "~{RESET}_17") (pintype "bidirectional"))
      (node (ref "R18") (pin "1") (pinfunction "1_1") (pintype "passive"))
      (node (ref "SW1") (pin "1") (pinfunction "P_1") (pintype "passive"))
    )
    (net (code "45") (name "/~{X-EN}") (class "Default")
      (node (ref "IC1") (pin "81") (pinfunction "P0[4]/I2SRX_CLK/RD2/CAP2[0]_81") (pintype "bidirectional"))
      (node (ref "P1") (pin "!EN") (pinfunction "~{ENABLE}_!EN") (pintype "input"))
    )
    (net (code "46") (name "/~{Y-EN}") (class "Default")
      (node (ref "IC1") (pin "48") (pinfunction "P0[10]/TXD2/SDA2/MAT3[0]_48") (pintype "bidirectional"))
      (node (ref "P2") (pin "!EN") (pinfunction "~{ENABLE}_!EN") (pintype "input"))
    )
    (net (code "47") (name "/~{Z-EN}") (class "Default")
      (node (ref "IC1") (pin "59") (pinfunction "P0[19]/DSR1/SDA1_59") (pintype "bidirectional"))
      (node (ref "P3") (pin "!EN") (pinfunction "~{ENABLE}_!EN") (pintype "input"))
    )
    (net (code "48") (name "3.3V") (class "Default")
      (node (ref "C18") (pin "2") (pinfunction "2_2") (pintype "passive"))
      (node (ref "C22") (pin "2") (pinfunction "2_2") (pintype "passive"))
      (node (ref "C23") (pin "2") (pinfunction "2_2") (pintype "passive"))
      (node (ref "C24") (pin "2") (pinfunction "2_2") (pintype "passive"))
      (node (ref "C25") (pin "2") (pinfunction "2_2") (pintype "passive"))
      (node (ref "C26") (pin "2") (pinfunction "2_2") (pintype "passive"))
      (node (ref "C27") (pin "2") (pinfunction "2_2") (pintype "passive"))
      (node (ref "C28") (pin "2") (pinfunction "2_2") (pintype "passive"))
      (node (ref "C8") (pin "1") (pinfunction "1_1") (pintype "passive"))
      (node (ref "CN110") (pin "2") (pinfunction "2_2") (pintype "passive"))
      (node (ref "CN111") (pin "2") (pinfunction "2_2") (pintype "passive"))
      (node (ref "CN112") (pin "2") (pinfunction "2_2") (pintype "passive"))
      (node (ref "CN113") (pin "2") (pinfunction "2_2") (pintype "passive"))
      (node (ref "CN114") (pin "2") (pinfunction "2_2") (pintype "passive"))
      (node (ref "CN115") (pin "2") (pinfunction "2_2") (pintype "passive"))
      (node (ref "CN150") (pin "4") (pinfunction "VDD_4") (pintype "bidirectional"))
      (node (ref "E-MS1") (pin "1") (pinfunction "1_1") (pintype "passive"))
      (node (ref "E-MS1") (pin "2") (pinfunction "2_2") (pintype "passive"))
      (node (ref "E-MS2") (pin "1") (pinfunction "1_1") (pintype "passive"))
      (node (ref "E-MS2") (pin "2") (pinfunction "2_2") (pintype "passive"))
      (node (ref "E-MS3") (pin "1") (pinfunction "1_1") (pintype "passive"))
      (node (ref "E-MS3") (pin "2") (pinfunction "2_2") (pintype "passive"))
      (node (ref "E-MS4") (pin "1") (pinfunction "1_1") (pintype "passive"))
      (node (ref "E-MS4") (pin "2") (pinfunction "2_2") (pintype "passive"))
      (node (ref "E-MS5") (pin "1") (pinfunction "1_1") (pintype "passive"))
      (node (ref "E-MS5") (pin "2") (pinfunction "2_2") (pintype "passive"))
      (node (ref "E-MS6") (pin "1") (pinfunction "1_1") (pintype "passive"))
      (node (ref "E-MS6") (pin "2") (pinfunction "2_2") (pintype "passive"))
      (node (ref "IC1") (pin "19") (pinfunction "VBAT_19") (pintype "bidirectional"))
      (node (ref "IC1") (pin "28") (pinfunction "VDD(3V3)1_28") (pintype "bidirectional"))
      (node (ref "IC1") (pin "42") (pinfunction "VDD(REG)(3V3)1_42") (pintype "bidirectional"))
      (node (ref "IC1") (pin "54") (pinfunction "VDD(3V3)2_54") (pintype "bidirectional"))
      (node (ref "IC1") (pin "71") (pinfunction "VDD(3V3)3_71") (pintype "bidirectional"))
      (node (ref "IC1") (pin "84") (pinfunction "VDD(REG)(3V3)2_84") (pintype "bidirectional"))
      (node (ref "IC1") (pin "96") (pinfunction "VDD(3V3)4_96") (pintype "bidirectional"))
      (node (ref "IC2") (pin "3") (pinfunction "VOUT_3") (pintype "passive"))
      (node (ref "L1") (pin "1") (pinfunction "1_1") (pintype "passive"))
      (node (ref "P1") (pin "MS1") (pinfunction "MS1_MS1") (pintype "input"))
      (node (ref "P1") (pin "MS2") (pinfunction "MS2_MS2") (pintype "input"))
      (node (ref "P1") (pin "MS3") (pinfunction "MS3_MS3") (pintype "input"))
      (node (ref "P1") (pin "VDD") (pinfunction "VDD_VDD") (pintype "power_in"))
      (node (ref "P2") (pin "MS1") (pinfunction "MS1_MS1") (pintype "input"))
      (node (ref "P2") (pin "MS2") (pinfunction "MS2_MS2") (pintype "input"))
      (node (ref "P2") (pin "MS3") (pinfunction "MS3_MS3") (pintype "input"))
      (node (ref "P2") (pin "VDD") (pinfunction "VDD_VDD") (pintype "power_in"))
      (node (ref "P3") (pin "MS1") (pinfunction "MS1_MS1") (pintype "input"))
      (node (ref "P3") (pin "MS2") (pinfunction "MS2_MS2") (pintype "input"))
      (node (ref "P3") (pin "MS3") (pinfunction "MS3_MS3") (pintype "input"))
      (node (ref "P3") (pin "VDD") (pinfunction "VDD_VDD") (pintype "power_in"))
      (node (ref "P4") (pin "MS1") (pinfunction "MS1_MS1") (pintype "input"))
      (node (ref "P4") (pin "MS2") (pinfunction "MS2_MS2") (pintype "input"))
      (node (ref "P4") (pin "MS3") (pinfunction "MS3_MS3") (pintype "input"))
      (node (ref "P4") (pin "VDD") (pinfunction "VDD_VDD") (pintype "power_in"))
      (node (ref "P5") (pin "MS1") (pinfunction "MS1_MS1") (pintype "input"))
      (node (ref "P5") (pin "MS2") (pinfunction "MS2_MS2") (pintype "input"))
      (node (ref "P5") (pin "MS3") (pinfunction "MS3_MS3") (pintype "input"))
      (node (ref "P5") (pin "VDD") (pinfunction "VDD_VDD") (pintype "power_in"))
      (node (ref "Q5") (pin "2") (pinfunction "S_2") (pintype "passive"))
      (node (ref "R17") (pin "2") (pinfunction "2_2") (pintype "passive"))
      (node (ref "R18") (pin "2") (pinfunction "2_2") (pintype "passive"))
      (node (ref "R19") (pin "2") (pinfunction "2_2") (pintype "passive"))
      (node (ref "R20") (pin "1") (pinfunction "1_1") (pintype "passive"))
      (node (ref "R21") (pin "1") (pinfunction "1_1") (pintype "passive"))
      (node (ref "R22") (pin "1") (pinfunction "1_1") (pintype "passive"))
      (node (ref "R23") (pin "1") (pinfunction "1_1") (pintype "passive"))
      (node (ref "R24") (pin "1") (pinfunction "1_1") (pintype "passive"))
      (node (ref "R4") (pin "2") (pinfunction "2_2") (pintype "passive"))
      (node (ref "X-MS1") (pin "1") (pinfunction "1_1") (pintype "passive"))
      (node (ref "X-MS1") (pin "2") (pinfunction "2_2") (pintype "passive"))
      (node (ref "X-MS2") (pin "1") (pinfunction "1_1") (pintype "passive"))
      (node (ref "X-MS2") (pin "2") (pinfunction "2_2") (pintype "passive"))
      (node (ref "X-MS3") (pin "1") (pinfunction "1_1") (pintype "passive"))
      (node (ref "X-MS3") (pin "2") (pinfunction "2_2") (pintype "passive"))
      (node (ref "Y-MS1") (pin "1") (pinfunction "1_1") (pintype "passive"))
      (node (ref "Y-MS1") (pin "2") (pinfunction "2_2") (pintype "passive"))
      (node (ref "Y-MS2") (pin "1") (pinfunction "1_1") (pintype "passive"))
      (node (ref "Y-MS2") (pin "2") (pinfunction "2_2") (pintype "passive"))
      (node (ref "Y-MS3") (pin "1") (pinfunction "1_1") (pintype "passive"))
      (node (ref "Y-MS3") (pin "2") (pinfunction "2_2") (pintype "passive"))
      (node (ref "Z-MS1") (pin "1") (pinfunction "1_1") (pintype "passive"))
      (node (ref "Z-MS1") (pin "2") (pinfunction "2_2") (pintype "passive"))
      (node (ref "Z-MS2") (pin "1") (pinfunction "1_1") (pintype "passive"))
      (node (ref "Z-MS2") (pin "2") (pinfunction "2_2") (pintype "passive"))
      (node (ref "Z-MS3") (pin "1") (pinfunction "1_1") (pintype "passive"))
      (node (ref "Z-MS3") (pin "2") (pinfunction "2_2") (pintype "passive"))
    )
    (net (code "49") (name "12V") (class "Default")
      (node (ref "C1") (pin "+") (pinfunction "+_+") (pintype "passive"))
      (node (ref "C2") (pin "+") (pinfunction "+_+") (pintype "passive"))
      (node (ref "C3") (pin "+") (pinfunction "+_+") (pintype "passive"))
      (node (ref "C4") (pin "+") (pinfunction "+_+") (pintype "passive"))
      (node (ref "C5") (pin "+") (pinfunction "+_+") (pintype "passive"))
      (node (ref "C6") (pin "+") (pinfunction "+_+") (pintype "passive"))
      (node (ref "C7") (pin "1") (pinfunction "1_1") (pintype "passive"))
      (node (ref "CN1") (pin "1") (pinfunction "S_1") (pintype "passive"))
      (node (ref "CN1") (pin "2") (pinfunction "S_2") (pintype "passive"))
      (node (ref "CN1") (pin "3") (pinfunction "S_3") (pintype "passive"))
      (node (ref "D1") (pin "1") (pinfunction "C_1") (pintype "passive"))
      (node (ref "FAN") (pin "2") (pinfunction "2_2") (pintype "passive"))
      (node (ref "HEATBED") (pin "2") (pinfunction "2_2") (pintype "passive"))
      (node (ref "HOTEND0") (pin "2") (pinfunction "2_2") (pintype "passive"))
      (node (ref "HOTEND1") (pin "2") (pinfunction "2_2") (pintype "passive"))
      (node (ref "IC2") (pin "1") (pinfunction "VIN_1") (pintype "passive"))
      (node (ref "P1") (pin "VMOT") (pinfunction "VMOT_VMOT") (pintype "power_in"))
      (node (ref "P2") (pin "VMOT") (pinfunction "VMOT_VMOT") (pintype "power_in"))
      (node (ref "P3") (pin "VMOT") (pinfunction "VMOT_VMOT") (pintype "power_in"))
      (node (ref "P4") (pin "VMOT") (pinfunction "VMOT_VMOT") (pintype "power_in"))
      (node (ref "P5") (pin "VMOT") (pinfunction "VMOT_VMOT") (pintype "power_in"))
    )
    (net (code "50") (name "AGND") (class "Default")
      (node (ref "C10") (pin "1") (pinfunction "1_1") (pintype "passive"))
      (node (ref "C11") (pin "1") (pinfunction "1_1") (pintype "passive"))
      (node (ref "C12") (pin "2") (pinfunction "2_2") (pintype "passive"))
      (node (ref "C19") (pin "2") (pinfunction "2_2") (pintype "passive"))
      (node (ref "C20") (pin "1") (pinfunction "1_1") (pintype "passive"))
      (node (ref "C21") (pin "2") (pinfunction "2_2") (pintype "passive"))
      (node (ref "C9") (pin "1") (pinfunction "1_1") (pintype "passive"))
      (node (ref "CN160") (pin "2") (pinfunction "2_2") (pintype "passive"))
      (node (ref "CN161") (pin "2") (pinfunction "2_2") (pintype "passive"))
      (node (ref "CN162") (pin "2") (pinfunction "2_2") (pintype "passive"))
      (node (ref "CN163") (pin "2") (pinfunction "2_2") (pintype "passive"))
      (node (ref "GND") (pin "2") (pinfunction "2_2") (pintype "passive"))
      (node (ref "IC1") (pin "11") (pinfunction "VSSA_11") (pintype "bidirectional"))
      (node (ref "IC1") (pin "15") (pinfunction "VREFN_15") (pintype "bidirectional"))
      (node (ref "IC4") (pin "3") (pinfunction "GND_3") (pintype "power_in"))
      (node (ref "IC4") (pin "4") (pinfunction "V-_4") (pintype "power_in"))
      (node (ref "IC4") (pin "8") (pinfunction "-IN_8") (pintype "bidirectional"))
    )
    (net (code "51") (name "GND") (class "Default")
      (node (ref "C1") (pin "-") (pinfunction "-_-") (pintype "passive"))
      (node (ref "C14") (pin "2") (pinfunction "2_2") (pintype "passive"))
      (node (ref "C15") (pin "2") (pinfunction "2_2") (pintype "passive"))
      (node (ref "C16") (pin "2") (pinfunction "2_2") (pintype "passive"))
      (node (ref "C17") (pin "2") (pinfunction "2_2") (pintype "passive"))
      (node (ref "C18") (pin "1") (pinfunction "1_1") (pintype "passive"))
      (node (ref "C2") (pin "-") (pinfunction "-_-") (pintype "passive"))
      (node (ref "C22") (pin "1") (pinfunction "1_1") (pintype "passive"))
      (node (ref "C23") (pin "1") (pinfunction "1_1") (pintype "passive"))
      (node (ref "C24") (pin "1") (pinfunction "1_1") (pintype "passive"))
      (node (ref "C25") (pin "1") (pinfunction "1_1") (pintype "passive"))
      (node (ref "C26") (pin "1") (pinfunction "1_1") (pintype "passive"))
      (node (ref "C27") (pin "1") (pinfunction "1_1") (pintype "passive"))
      (node (ref "C28") (pin "1") (pinfunction "1_1") (pintype "passive"))
      (node (ref "C3") (pin "-") (pinfunction "-_-") (pintype "passive"))
      (node (ref "C4") (pin "-") (pinfunction "-_-") (pintype "passive"))
      (node (ref "C5") (pin "-") (pinfunction "-_-") (pintype "passive"))
      (node (ref "C6") (pin "-") (pinfunction "-_-") (pintype "passive"))
      (node (ref "C7") (pin "2") (pinfunction "2_2") (pintype "passive"))
      (node (ref "C8") (pin "2") (pinfunction "2_2") (pintype "passive"))
      (node (ref "CN1") (pin "4") (pinfunction "S_4") (pintype "passive"))
      (node (ref "CN1") (pin "5") (pinfunction "S_5") (pintype "passive"))
      (node (ref "CN1") (pin "6") (pinfunction "S_6") (pintype "passive"))
      (node (ref "CN110") (pin "3") (pinfunction "3_3") (pintype "passive"))
      (node (ref "CN111") (pin "3") (pinfunction "3_3") (pintype "passive"))
      (node (ref "CN112") (pin "3") (pinfunction "3_3") (pintype "passive"))
      (node (ref "CN113") (pin "3") (pinfunction "3_3") (pintype "passive"))
      (node (ref "CN114") (pin "3") (pinfunction "3_3") (pintype "passive"))
      (node (ref "CN115") (pin "3") (pinfunction "3_3") (pintype "passive"))
      (node (ref "CN120") (pin "1") (pinfunction "1_1") (pintype "passive"))
      (node (ref "CN121") (pin "1") (pinfunction "1_1") (pintype "passive"))
      (node (ref "CN130") (pin "1") (pinfunction "1_1") (pintype "passive"))
      (node (ref "CN131") (pin "2") (pinfunction "2_2") (pintype "passive"))
      (node (ref "CN150") (pin "6") (pinfunction "GND_6") (pintype "bidirectional"))
      (node (ref "CN150") (pin "GND1") (pinfunction "SHIELD_GND1") (pintype "bidirectional"))
      (node (ref "CN150") (pin "GND2") (pinfunction "SHIELD_GND2") (pintype "bidirectional"))
      (node (ref "CN150") (pin "GND3") (pinfunction "SHIELD_GND3") (pintype "bidirectional"))
      (node (ref "CN150") (pin "GND4") (pinfunction "SHIELD_GND4") (pintype "bidirectional"))
      (node (ref "CN2") (pin "5") (pinfunction "5_5") (pintype "input"))
      (node (ref "CN2") (pin "M1") (pinfunction "S1_M1") (pintype "passive"))
      (node (ref "CN2") (pin "M2") (pinfunction "S2_M2") (pintype "passive"))
      (node (ref "CN2") (pin "M3") (pinfunction "S3_M3") (pintype "passive"))
      (node (ref "CN2") (pin "M4") (pinfunction "S4_M4") (pintype "passive"))
      (node (ref "D1") (pin "2") (pinfunction "A_2") (pintype "passive"))
      (node (ref "GND") (pin "1") (pinfunction "1_1") (pintype "passive"))
      (node (ref "HOLE1") (pin "GND") (pinfunction "GND-SCREW_GND") (pintype "bidirectional"))
      (node (ref "HOLE2") (pin "GND") (pinfunction "GND-SCREW_GND") (pintype "bidirectional"))
      (node (ref "HOLE3") (pin "GND") (pinfunction "GND-SCREW_GND") (pintype "bidirectional"))
      (node (ref "HOLE4") (pin "GND") (pinfunction "GND-SCREW_GND") (pintype "bidirectional"))
      (node (ref "IC1") (pin "31") (pinfunction "VSS1_31") (pintype "bidirectional"))
      (node (ref "IC1") (pin "41") (pinfunction "VSS2_41") (pintype "bidirectional"))
      (node (ref "IC1") (pin "55") (pinfunction "VSS3_55") (pintype "bidirectional"))
      (node (ref "IC1") (pin "72") (pinfunction "VSS4_72") (pintype "bidirectional"))
      (node (ref "IC1") (pin "83") (pinfunction "VSS6_83") (pintype "bidirectional"))
      (node (ref "IC1") (pin "97") (pinfunction "VSS5_97") (pintype "bidirectional"))
      (node (ref "IC2") (pin "2") (pinfunction "GND_2") (pintype "passive"))
      (node (ref "LD0") (pin "C") (pinfunction "C_C") (pintype "passive"))
      (node (ref "LD1") (pin "C") (pinfunction "C_C") (pintype "passive"))
      (node (ref "LD2") (pin "C") (pinfunction "C_C") (pintype "passive"))
      (node (ref "LD3") (pin "C") (pinfunction "C_C") (pintype "passive"))
      (node (ref "LD4") (pin "C") (pinfunction "C_C") (pintype "passive"))
      (node (ref "P1") (pin "GNDMOT") (pinfunction "GNDMOT_GNDMOT") (pintype "power_in"))
      (node (ref "P1") (pin "GNDVDD") (pinfunction "GNDVDD_GNDVDD") (pintype "power_in"))
      (node (ref "P2") (pin "GNDMOT") (pinfunction "GNDMOT_GNDMOT") (pintype "power_in"))
      (node (ref "P2") (pin "GNDVDD") (pinfunction "GNDVDD_GNDVDD") (pintype "power_in"))
      (node (ref "P3") (pin "GNDMOT") (pinfunction "GNDMOT_GNDMOT") (pintype "power_in"))
      (node (ref "P3") (pin "GNDVDD") (pinfunction "GNDVDD_GNDVDD") (pintype "power_in"))
      (node (ref "P4") (pin "GNDMOT") (pinfunction "GNDMOT_GNDMOT") (pintype "power_in"))
      (node (ref "P4") (pin "GNDVDD") (pinfunction "GNDVDD_GNDVDD") (pintype "power_in"))
      (node (ref "P5") (pin "GNDMOT") (pinfunction "GNDMOT_GNDMOT") (pintype "power_in"))
      (node (ref "P5") (pin "GNDVDD") (pinfunction "GNDVDD_GNDVDD") (pintype "power_in"))
      (node (ref "Q1") (pin "1") (pinfunction "S_1") (pintype "passive"))
      (node (ref "Q1") (pin "2") (pinfunction "S_2") (pintype "passive"))
      (node (ref "Q1") (pin "3") (pinfunction "S_3") (pintype "passive"))
      (node (ref "Q2") (pin "1") (pinfunction "S_1") (pintype "passive"))
      (node (ref "Q2") (pin "2") (pinfunction "S_2") (pintype "passive"))
      (node (ref "Q2") (pin "3") (pinfunction "S_3") (pintype "passive"))
      (node (ref "Q3") (pin "1") (pinfunction "S_1") (pintype "passive"))
      (node (ref "Q3") (pin "2") (pinfunction "S_2") (pintype "passive"))
      (node (ref "Q3") (pin "3") (pinfunction "S_3") (pintype "passive"))
      (node (ref "Q4") (pin "2") (pinfunction "S_2") (pintype "passive"))
      (node (ref "R13") (pin "2") (pinfunction "2_2") (pintype "passive"))
      (node (ref "R14") (pin "2") (pinfunction "2_2") (pintype "passive"))
      (node (ref "R15") (pin "2") (pinfunction "2_2") (pintype "passive"))
      (node (ref "R16") (pin "2") (pinfunction "2_2") (pintype "passive"))
      (node (ref "R20") (pin "2") (pinfunction "2_2") (pintype "passive"))
      (node (ref "R21") (pin "2") (pinfunction "2_2") (pintype "passive"))
      (node (ref "R22") (pin "2") (pinfunction "2_2") (pintype "passive"))
      (node (ref "R23") (pin "2") (pinfunction "2_2") (pintype "passive"))
      (node (ref "R24") (pin "2") (pinfunction "2_2") (pintype "passive"))
      (node (ref "SW1") (pin "2") (pinfunction "S_2") (pintype "passive"))
      (node (ref "SW1") (pin "3") (pinfunction "S_3") (pintype "passive"))
      (node (ref "SW1") (pin "4") (pinfunction "S_4") (pintype "passive"))
      (node (ref "X1") (pin "2") (pinfunction "2_2") (pintype "passive"))
      (node (ref "X1") (pin "4") (pinfunction "4_4") (pintype "passive"))
    )
    (net (code "52") (name "Net-(C16-Pad1)") (class "Default")
      (node (ref "C16") (pin "1") (pinfunction "1_1") (pintype "passive"))
      (node (ref "CN2") (pin "2") (pinfunction "2_2") (pintype "input"))
      (node (ref "R1") (pin "2") (pinfunction "2_2") (pintype "passive"))
    )
    (net (code "53") (name "Net-(C17-Pad1)") (class "Default")
      (node (ref "C17") (pin "1") (pinfunction "1_1") (pintype "passive"))
      (node (ref "CN2") (pin "3") (pinfunction "3_3") (pintype "input"))
      (node (ref "R2") (pin "2") (pinfunction "2_2") (pintype "passive"))
      (node (ref "R3") (pin "2") (pinfunction "2_2") (pintype "passive"))
    )
    (net (code "54") (name "Net-(CN121-Pad2)") (class "Default")
      (node (ref "CN121") (pin "2") (pinfunction "2_2") (pintype "passive"))
      (node (ref "R9") (pin "1") (pinfunction "1_1") (pintype "passive"))
    )
    (net (code "55") (name "Net-(IC1-XTAL1)") (class "Default")
      (node (ref "C15") (pin "1") (pinfunction "1_1") (pintype "passive"))
      (node (ref "IC1") (pin "22") (pinfunction "XTAL1_22") (pintype "bidirectional"))
      (node (ref "X1") (pin "3") (pinfunction "3_3") (pintype "passive"))
    )
    (net (code "56") (name "Net-(IC1-XTAL2)") (class "Default")
      (node (ref "C14") (pin "1") (pinfunction "1_1") (pintype "passive"))
      (node (ref "IC1") (pin "23") (pinfunction "XTAL2_23") (pintype "bidirectional"))
      (node (ref "X1") (pin "1") (pinfunction "1_1") (pintype "passive"))
    )
    (net (code "57") (name "Net-(IC4-+IN)") (class "Default")
      (node (ref "C20") (pin "2") (pinfunction "2_2") (pintype "passive"))
      (node (ref "CN163") (pin "1") (pinfunction "1_1") (pintype "passive"))
      (node (ref "IC4") (pin "1") (pinfunction "+IN_1") (pintype "bidirectional"))
    )
    (net (code "58") (name "Net-(LD0-PadA)") (class "Default")
      (node (ref "LD0") (pin "A") (pinfunction "A_A") (pintype "passive"))
      (node (ref "R4") (pin "1") (pinfunction "1_1") (pintype "passive"))
    )
    (net (code "59") (name "Net-(LD1-PadA)") (class "Default")
      (node (ref "LD1") (pin "A") (pinfunction "A_A") (pintype "passive"))
      (node (ref "R5") (pin "1") (pinfunction "1_1") (pintype "passive"))
    )
    (net (code "60") (name "Net-(LD2-PadA)") (class "Default")
      (node (ref "LD2") (pin "A") (pinfunction "A_A") (pintype "passive"))
      (node (ref "R6") (pin "1") (pinfunction "1_1") (pintype "passive"))
    )
    (net (code "61") (name "Net-(LD3-PadA)") (class "Default")
      (node (ref "LD3") (pin "A") (pinfunction "A_A") (pintype "passive"))
      (node (ref "R7") (pin "1") (pinfunction "1_1") (pintype "passive"))
    )
    (net (code "62") (name "Net-(LD4-PadA)") (class "Default")
      (node (ref "LD4") (pin "A") (pinfunction "A_A") (pintype "passive"))
      (node (ref "R8") (pin "1") (pinfunction "1_1") (pintype "passive"))
    )
    (net (code "63") (name "Net-(P1-MOT-1A)") (class "Default")
      (node (ref "CN101") (pin "3") (pinfunction "3_3") (pintype "passive"))
      (node (ref "P1") (pin "1A") (pinfunction "MOT-1A_1A") (pintype "power_in"))
    )
    (net (code "64") (name "Net-(P1-MOT-1B)") (class "Default")
      (node (ref "CN101") (pin "4") (pinfunction "4_4") (pintype "passive"))
      (node (ref "P1") (pin "1B") (pinfunction "MOT-1B_1B") (pintype "power_in"))
    )
    (net (code "65") (name "Net-(P1-MOT-2A)") (class "Default")
      (node (ref "CN101") (pin "2") (pinfunction "2_2") (pintype "passive"))
      (node (ref "P1") (pin "2A") (pinfunction "MOT-2A_2A") (pintype "power_in"))
    )
    (net (code "66") (name "Net-(P1-MOT-2B)") (class "Default")
      (node (ref "CN101") (pin "1") (pinfunction "1_1") (pintype "passive"))
      (node (ref "P1") (pin "2B") (pinfunction "MOT-2B_2B") (pintype "power_in"))
    )
    (net (code "67") (name "Net-(P1-~{RESET})") (class "Default")
      (node (ref "P1") (pin "!RST") (pinfunction "~{RESET}_!RST") (pintype "input"))
      (node (ref "P1") (pin "!SLP") (pinfunction "~{SLEEP}_!SLP") (pintype "input"))
    )
    (net (code "68") (name "Net-(P2-MOT-1A)") (class "Default")
      (node (ref "CN102") (pin "3") (pinfunction "3_3") (pintype "passive"))
      (node (ref "P2") (pin "1A") (pinfunction "MOT-1A_1A") (pintype "power_in"))
    )
    (net (code "69") (name "Net-(P2-MOT-1B)") (class "Default")
      (node (ref "CN102") (pin "4") (pinfunction "4_4") (pintype "passive"))
      (node (ref "P2") (pin "1B") (pinfunction "MOT-1B_1B") (pintype "power_in"))
    )
    (net (code "70") (name "Net-(P2-MOT-2A)") (class "Default")
      (node (ref "CN102") (pin "2") (pinfunction "2_2") (pintype "passive"))
      (node (ref "P2") (pin "2A") (pinfunction "MOT-2A_2A") (pintype "power_in"))
    )
    (net (code "71") (name "Net-(P2-MOT-2B)") (class "Default")
      (node (ref "CN102") (pin "1") (pinfunction "1_1") (pintype "passive"))
      (node (ref "P2") (pin "2B") (pinfunction "MOT-2B_2B") (pintype "power_in"))
    )
    (net (code "72") (name "Net-(P2-~{RESET})") (class "Default")
      (node (ref "P2") (pin "!RST") (pinfunction "~{RESET}_!RST") (pintype "input"))
      (node (ref "P2") (pin "!SLP") (pinfunction "~{SLEEP}_!SLP") (pintype "input"))
    )
    (net (code "73") (name "Net-(P3-MOT-1A)") (class "Default")
      (node (ref "CN103") (pin "3") (pinfunction "3_3") (pintype "passive"))
      (node (ref "CN104") (pin "3") (pinfunction "3_3") (pintype "passive"))
      (node (ref "P3") (pin "1A") (pinfunction "MOT-1A_1A") (pintype "power_in"))
    )
    (net (code "74") (name "Net-(P3-MOT-1B)") (class "Default")
      (node (ref "CN103") (pin "4") (pinfunction "4_4") (pintype "passive"))
      (node (ref "CN104") (pin "4") (pinfunction "4_4") (pintype "passive"))
      (node (ref "P3") (pin "1B") (pinfunction "MOT-1B_1B") (pintype "power_in"))
    )
    (net (code "75") (name "Net-(P3-MOT-2A)") (class "Default")
      (node (ref "CN103") (pin "2") (pinfunction "2_2") (pintype "passive"))
      (node (ref "CN104") (pin "2") (pinfunction "2_2") (pintype "passive"))
      (node (ref "P3") (pin "2A") (pinfunction "MOT-2A_2A") (pintype "power_in"))
    )
    (net (code "76") (name "Net-(P3-MOT-2B)") (class "Default")
      (node (ref "CN103") (pin "1") (pinfunction "1_1") (pintype "passive"))
      (node (ref "CN104") (pin "1") (pinfunction "1_1") (pintype "passive"))
      (node (ref "P3") (pin "2B") (pinfunction "MOT-2B_2B") (pintype "power_in"))
    )
    (net (code "77") (name "Net-(P3-~{RESET})") (class "Default")
      (node (ref "P3") (pin "!RST") (pinfunction "~{RESET}_!RST") (pintype "input"))
      (node (ref "P3") (pin "!SLP") (pinfunction "~{SLEEP}_!SLP") (pintype "input"))
    )
    (net (code "78") (name "Net-(P4-MOT-1A)") (class "Default")
      (node (ref "CN105") (pin "3") (pinfunction "3_3") (pintype "passive"))
      (node (ref "P4") (pin "1A") (pinfunction "MOT-1A_1A") (pintype "power_in"))
    )
    (net (code "79") (name "Net-(P4-MOT-1B)") (class "Default")
      (node (ref "CN105") (pin "4") (pinfunction "4_4") (pintype "passive"))
      (node (ref "P4") (pin "1B") (pinfunction "MOT-1B_1B") (pintype "power_in"))
    )
    (net (code "80") (name "Net-(P4-MOT-2A)") (class "Default")
      (node (ref "CN105") (pin "2") (pinfunction "2_2") (pintype "passive"))
      (node (ref "P4") (pin "2A") (pinfunction "MOT-2A_2A") (pintype "power_in"))
    )
    (net (code "81") (name "Net-(P4-MOT-2B)") (class "Default")
      (node (ref "CN105") (pin "1") (pinfunction "1_1") (pintype "passive"))
      (node (ref "P4") (pin "2B") (pinfunction "MOT-2B_2B") (pintype "power_in"))
    )
    (net (code "82") (name "Net-(P4-~{RESET})") (class "Default")
      (node (ref "P4") (pin "!RST") (pinfunction "~{RESET}_!RST") (pintype "input"))
      (node (ref "P4") (pin "!SLP") (pinfunction "~{SLEEP}_!SLP") (pintype "input"))
    )
    (net (code "83") (name "Net-(P5-MOT-1A)") (class "Default")
      (node (ref "CN106") (pin "3") (pinfunction "3_3") (pintype "passive"))
      (node (ref "P5") (pin "1A") (pinfunction "MOT-1A_1A") (pintype "power_in"))
    )
    (net (code "84") (name "Net-(P5-MOT-1B)") (class "Default")
      (node (ref "CN106") (pin "4") (pinfunction "4_4") (pintype "passive"))
      (node (ref "P5") (pin "1B") (pinfunction "MOT-1B_1B") (pintype "power_in"))
    )
    (net (code "85") (name "Net-(P5-MOT-2A)") (class "Default")
      (node (ref "CN106") (pin "2") (pinfunction "2_2") (pintype "passive"))
      (node (ref "P5") (pin "2A") (pinfunction "MOT-2A_2A") (pintype "power_in"))
    )
    (net (code "86") (name "Net-(P5-MOT-2B)") (class "Default")
      (node (ref "CN106") (pin "1") (pinfunction "1_1") (pintype "passive"))
      (node (ref "P5") (pin "2B") (pinfunction "MOT-2B_2B") (pintype "power_in"))
    )
    (net (code "87") (name "Net-(P5-~{RESET})") (class "Default")
      (node (ref "P5") (pin "!RST") (pinfunction "~{RESET}_!RST") (pintype "input"))
      (node (ref "P5") (pin "!SLP") (pinfunction "~{SLEEP}_!SLP") (pintype "input"))
    )
    (net (code "88") (name "Net-(Q1-D)") (class "Default")
      (node (ref "HOTEND0") (pin "1") (pinfunction "1_1") (pintype "passive"))
      (node (ref "Q1") (pin "MB") (pinfunction "D_MB") (pintype "passive"))
    )
    (net (code "89") (name "Net-(Q2-D)") (class "Default")
      (node (ref "HEATBED") (pin "1") (pinfunction "1_1") (pintype "passive"))
      (node (ref "Q2") (pin "MB") (pinfunction "D_MB") (pintype "passive"))
    )
    (net (code "90") (name "Net-(Q3-D)") (class "Default")
      (node (ref "HOTEND1") (pin "1") (pinfunction "1_1") (pintype "passive"))
      (node (ref "Q3") (pin "MB") (pinfunction "D_MB") (pintype "passive"))
    )
    (net (code "91") (name "Net-(Q4-D)") (class "Default")
      (node (ref "FAN") (pin "1") (pinfunction "1_1") (pintype "passive"))
      (node (ref "Q4") (pin "3") (pinfunction "D_3") (pintype "passive"))
    )
    (net (code "92") (name "Net-(Q5-D)") (class "Default")
      (node (ref "Q5") (pin "3") (pinfunction "D_3") (pintype "passive"))
      (node (ref "R3") (pin "1") (pinfunction "1_1") (pintype "passive"))
    )
    (net (code "93") (name "unconnected-(CN2-Pad1)") (class "Default")
      (node (ref "CN2") (pin "1") (pinfunction "1_1") (pintype "input"))
    )
    (net (code "94") (name "unconnected-(CN2-Pad4)") (class "Default")
      (node (ref "CN2") (pin "4") (pinfunction "4_4") (pintype "input"))
    )
    (net (code "95") (name "unconnected-(CN131-Pad1)") (class "Default")
      (node (ref "CN131") (pin "1") (pinfunction "1_1") (pintype "passive"))
    )
    (net (code "96") (name "unconnected-(CN131-Pad5)") (class "Default")
      (node (ref "CN131") (pin "5") (pinfunction "5_5") (pintype "passive"))
    )
    (net (code "97") (name "unconnected-(CN131-Pad6)") (class "Default")
      (node (ref "CN131") (pin "6") (pinfunction "6_6") (pintype "passive"))
    )
    (net (code "98") (name "unconnected-(CN150-NC-Pad1)") (class "Default")
      (node (ref "CN150") (pin "1") (pinfunction "NC_1") (pintype "bidirectional"))
    )
    (net (code "99") (name "unconnected-(CN150-NC-Pad8)") (class "Default")
      (node (ref "CN150") (pin "8") (pinfunction "NC_8") (pintype "bidirectional"))
    )
    (net (code "100") (name "unconnected-(CN150-PadCD1)") (class "Default")
      (node (ref "CN150") (pin "CD1") (pinfunction "CD1_CD1") (pintype "bidirectional"))
    )
    (net (code "101") (name "unconnected-(CN150-PadCD2)") (class "Default")
      (node (ref "CN150") (pin "CD2") (pinfunction "CD2_CD2") (pintype "bidirectional"))
    )
    (net (code "102") (name "unconnected-(IC1-NC-Pad13)") (class "Default")
      (node (ref "IC1") (pin "13") (pinfunction "NC_13") (pintype "bidirectional"))
    )
    (net (code "103") (name "unconnected-(IC1-P0[0]{slash}RD1{slash}TXD3{slash}SDA1-Pad46)") (class "Default")
      (node (ref "IC1") (pin "46") (pinfunction "P0[0]/RD1/TXD3/SDA1_46") (pintype "bidirectional"))
    )
    (net (code "104") (name "unconnected-(IC1-P0[1]{slash}TD1{slash}RXD3{slash}SCL1-Pad47)") (class "Default")
      (node (ref "IC1") (pin "47") (pinfunction "P0[1]/TD1/RXD3/SCL1_47") (pintype "bidirectional"))
    )
    (net (code "105") (name "unconnected-(IC1-P0[15]{slash}TXD1{slash}SCK0{slash}SCK-Pad62)") (class "Default")
      (node (ref "IC1") (pin "62") (pinfunction "P0[15]/TXD1/SCK0/SCK_62") (pintype "bidirectional"))
    )
    (net (code "106") (name "unconnected-(IC1-P0[16]{slash}RXD1{slash}SSEL0{slash}SSEL-Pad63)") (class "Default")
      (node (ref "IC1") (pin "63") (pinfunction "P0[16]/RXD1/SSEL0/SSEL_63") (pintype "bidirectional"))
    )
    (net (code "107") (name "unconnected-(IC1-P0[17]{slash}CTS1{slash}MISO0{slash}MISO-Pad61)") (class "Default")
      (node (ref "IC1") (pin "61") (pinfunction "P0[17]/CTS1/MISO0/MISO_61") (pintype "bidirectional"))
    )
    (net (code "108") (name "unconnected-(IC1-P0[18]{slash}DCD1{slash}MOSI0{slash}MOSI-Pad60)") (class "Default")
      (node (ref "IC1") (pin "60") (pinfunction "P0[18]/DCD1/MOSI0/MOSI_60") (pintype "bidirectional"))
    )
    (net (code "109") (name "unconnected-(IC1-P0[27]{slash}SDA0{slash}USB_SDA-Pad25)") (class "Default")
      (node (ref "IC1") (pin "25") (pinfunction "P0[27]/SDA0/USB_SDA_25") (pintype "bidirectional"))
    )
    (net (code "110") (name "unconnected-(IC1-P0[28]{slash}SCL0{slash}USB_SCL-Pad24)") (class "Default")
      (node (ref "IC1") (pin "24") (pinfunction "P0[28]/SCL0/USB_SCL_24") (pintype "bidirectional"))
    )
    (net (code "111") (name "unconnected-(IC1-P1[0]{slash}ENET_TXD0-Pad95)") (class "Default")
      (node (ref "IC1") (pin "95") (pinfunction "P1[0]/ENET_TXD0_95") (pintype "bidirectional"))
    )
    (net (code "112") (name "unconnected-(IC1-P1[1]{slash}ENET_TXD1-Pad94)") (class "Default")
      (node (ref "IC1") (pin "94") (pinfunction "P1[1]/ENET_TXD1_94") (pintype "bidirectional"))
    )
    (net (code "113") (name "unconnected-(IC1-P1[4]{slash}ENET_TX_EN-Pad93)") (class "Default")
      (node (ref "IC1") (pin "93") (pinfunction "P1[4]/ENET_TX_EN_93") (pintype "bidirectional"))
    )
    (net (code "114") (name "unconnected-(IC1-P1[8]{slash}ENET_CRS-Pad92)") (class "Default")
      (node (ref "IC1") (pin "92") (pinfunction "P1[8]/ENET_CRS_92") (pintype "bidirectional"))
    )
    (net (code "115") (name "unconnected-(IC1-P1[9]{slash}ENET_RXD0-Pad91)") (class "Default")
      (node (ref "IC1") (pin "91") (pinfunction "P1[9]/ENET_RXD0_91") (pintype "bidirectional"))
    )
    (net (code "116") (name "unconnected-(IC1-P1[10]{slash}ENET_RXD1-Pad90)") (class "Default")
      (node (ref "IC1") (pin "90") (pinfunction "P1[10]/ENET_RXD1_90") (pintype "bidirectional"))
    )
    (net (code "117") (name "unconnected-(IC1-P1[14]{slash}ENET_RX_ER-Pad89)") (class "Default")
      (node (ref "IC1") (pin "89") (pinfunction "P1[14]/ENET_RX_ER_89") (pintype "bidirectional"))
    )
    (net (code "118") (name "unconnected-(IC1-P1[15]{slash}ENET_REF_CLK-Pad88)") (class "Default")
      (node (ref "IC1") (pin "88") (pinfunction "P1[15]/ENET_REF_CLK_88") (pintype "bidirectional"))
    )
    (net (code "119") (name "unconnected-(IC1-P1[16]{slash}ENET_MDC-Pad87)") (class "Default")
      (node (ref "IC1") (pin "87") (pinfunction "P1[16]/ENET_MDC_87") (pintype "bidirectional"))
    )
    (net (code "120") (name "unconnected-(IC1-P1[17]{slash}ENET_MDIO-Pad86)") (class "Default")
      (node (ref "IC1") (pin "86") (pinfunction "P1[17]/ENET_MDIO_86") (pintype "bidirectional"))
    )
    (net (code "121") (name "unconnected-(IC1-P1[22]{slash}MCOB0{slash}USB_PWRD{slash}MAT1[0]-Pad36)") (class "Default")
      (node (ref "IC1") (pin "36") (pinfunction "P1[22]/MCOB0/USB_PWRD/MAT1[0]_36") (pintype "bidirectional"))
    )
    (net (code "122") (name "unconnected-(IC1-P1[23]{slash}MCI1{slash}PWM1[4]{slash}MISO0-Pad37)") (class "Default")
      (node (ref "IC1") (pin "37") (pinfunction "P1[23]/MCI1/PWM1[4]/MISO0_37") (pintype "bidirectional"))
    )
    (net (code "123") (name "unconnected-(IC1-P1[30]{slash}VBUS{slash}AD0[4]-Pad21)") (class "Default")
      (node (ref "IC1") (pin "21") (pinfunction "P1[30]/VBUS/AD0[4]_21") (pintype "bidirectional"))
    )
    (net (code "124") (name "unconnected-(IC1-P1[31]{slash}SCK1{slash}AD0[5]-Pad20)") (class "Default")
      (node (ref "IC1") (pin "20") (pinfunction "P1[31]/SCK1/AD0[5]_20") (pintype "bidirectional"))
    )
    (net (code "125") (name "unconnected-(IC1-P2[11]{slash}EINT1{slash}I2STX_CLK-Pad52)") (class "Default")
      (node (ref "IC1") (pin "52") (pinfunction "P2[11]/EINT1/I2STX_CLK_52") (pintype "bidirectional"))
    )
    (net (code "126") (name "unconnected-(IC1-P3[25]{slash}MAT0[0]{slash}PWM1[2]-Pad27)") (class "Default")
      (node (ref "IC1") (pin "27") (pinfunction "P3[25]/MAT0[0]/PWM1[2]_27") (pintype "bidirectional"))
    )
    (net (code "127") (name "unconnected-(IC1-P3[26]{slash}STCLK{slash}MAT0[1]{slash}PWM1[3]-Pad26)") (class "Default")
      (node (ref "IC1") (pin "26") (pinfunction "P3[26]/STCLK/MAT0[1]/PWM1[3]_26") (pintype "bidirectional"))
    )
    (net (code "128") (name "unconnected-(IC1-RTCK-Pad100)") (class "Default")
      (node (ref "IC1") (pin "100") (pinfunction "RTCK_100") (pintype "bidirectional"))
    )
    (net (code "129") (name "unconnected-(IC1-RTCX1-Pad16)") (class "Default")
      (node (ref "IC1") (pin "16") (pinfunction "RTCX1_16") (pintype "bidirectional"))
    )
    (net (code "130") (name "unconnected-(IC1-RTCX2-Pad18)") (class "Default")
      (node (ref "IC1") (pin "18") (pinfunction "RTCX2_18") (pintype "bidirectional"))
    )
    (net (code "131") (name "unconnected-(IC1-TCK{slash}SWDCLK-Pad5)") (class "Default")
      (node (ref "IC1") (pin "5") (pinfunction "TCK/SWDCLK_5") (pintype "bidirectional"))
    )
    (net (code "132") (name "unconnected-(IC1-TDI-Pad2)") (class "Default")
      (node (ref "IC1") (pin "2") (pinfunction "TDI_2") (pintype "bidirectional"))
    )
    (net (code "133") (name "unconnected-(IC1-TDO{slash}SWO-Pad1)") (class "Default")
      (node (ref "IC1") (pin "1") (pinfunction "TDO/SWO_1") (pintype "bidirectional"))
    )
    (net (code "134") (name "unconnected-(IC1-TMS{slash}SWDIO-Pad3)") (class "Default")
      (node (ref "IC1") (pin "3") (pinfunction "TMS/SWDIO_3") (pintype "bidirectional"))
    )
    (net (code "135") (name "unconnected-(IC1-~{RSTOUT}-Pad14)") (class "Default")
      (node (ref "IC1") (pin "14") (pinfunction "~{RSTOUT}_14") (pintype "bidirectional"))
    )
    (net (code "136") (name "unconnected-(IC1-~{TRST}-Pad4)") (class "Default")
      (node (ref "IC1") (pin "4") (pinfunction "~{TRST}_4") (pintype "bidirectional"))
    )
    (net (code "137") (name "unconnected-(IC4-HYS-Pad2)") (class "Default")
      (node (ref "IC4") (pin "2") (pinfunction "HYS_2") (pintype "bidirectional"))
    )
  )
)
